# SEGmeterShield15.net
KiCad netlist of a schematic drawn in EAGLE
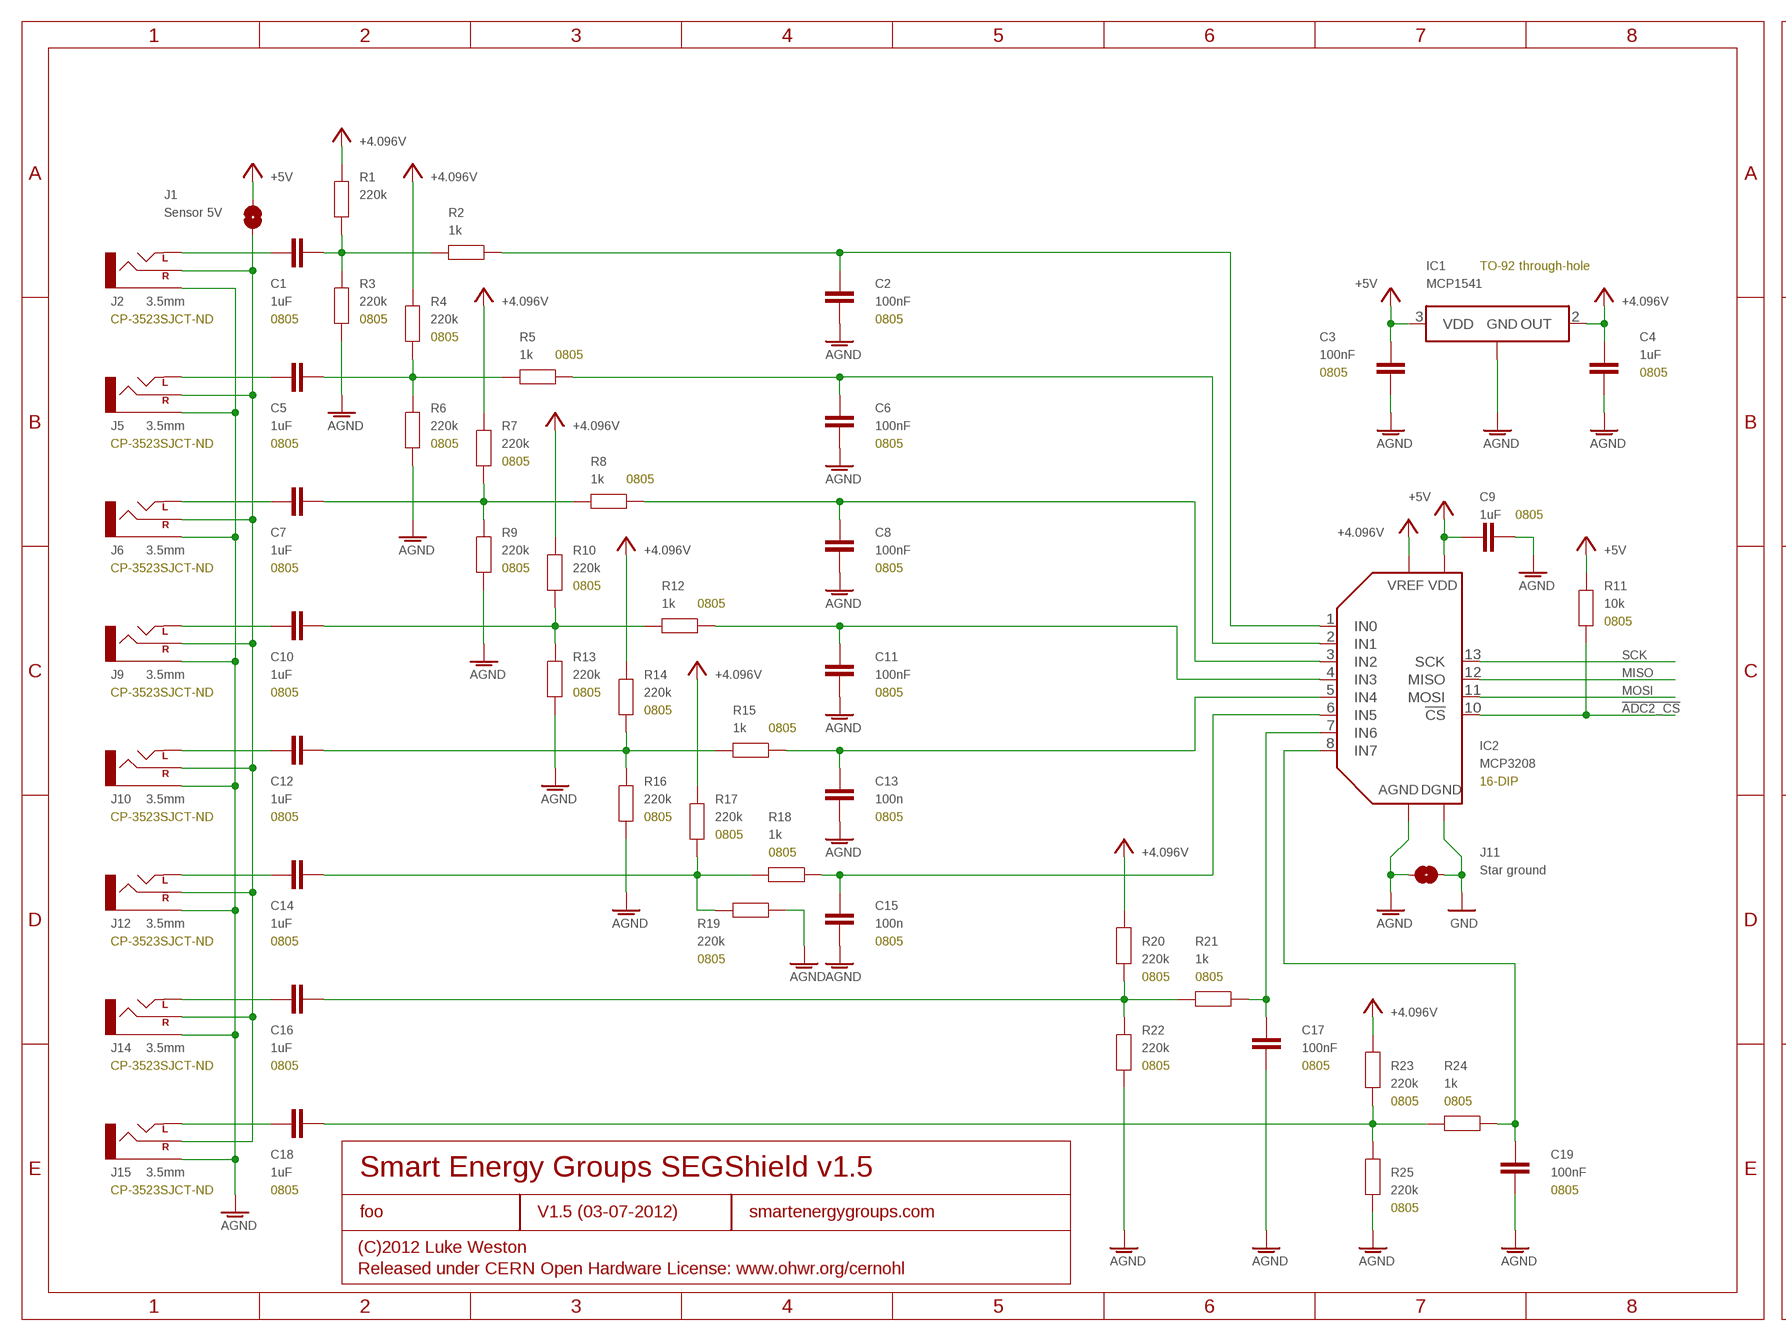
[diagram p0: schematic, sheet 1, part 1 of 2]
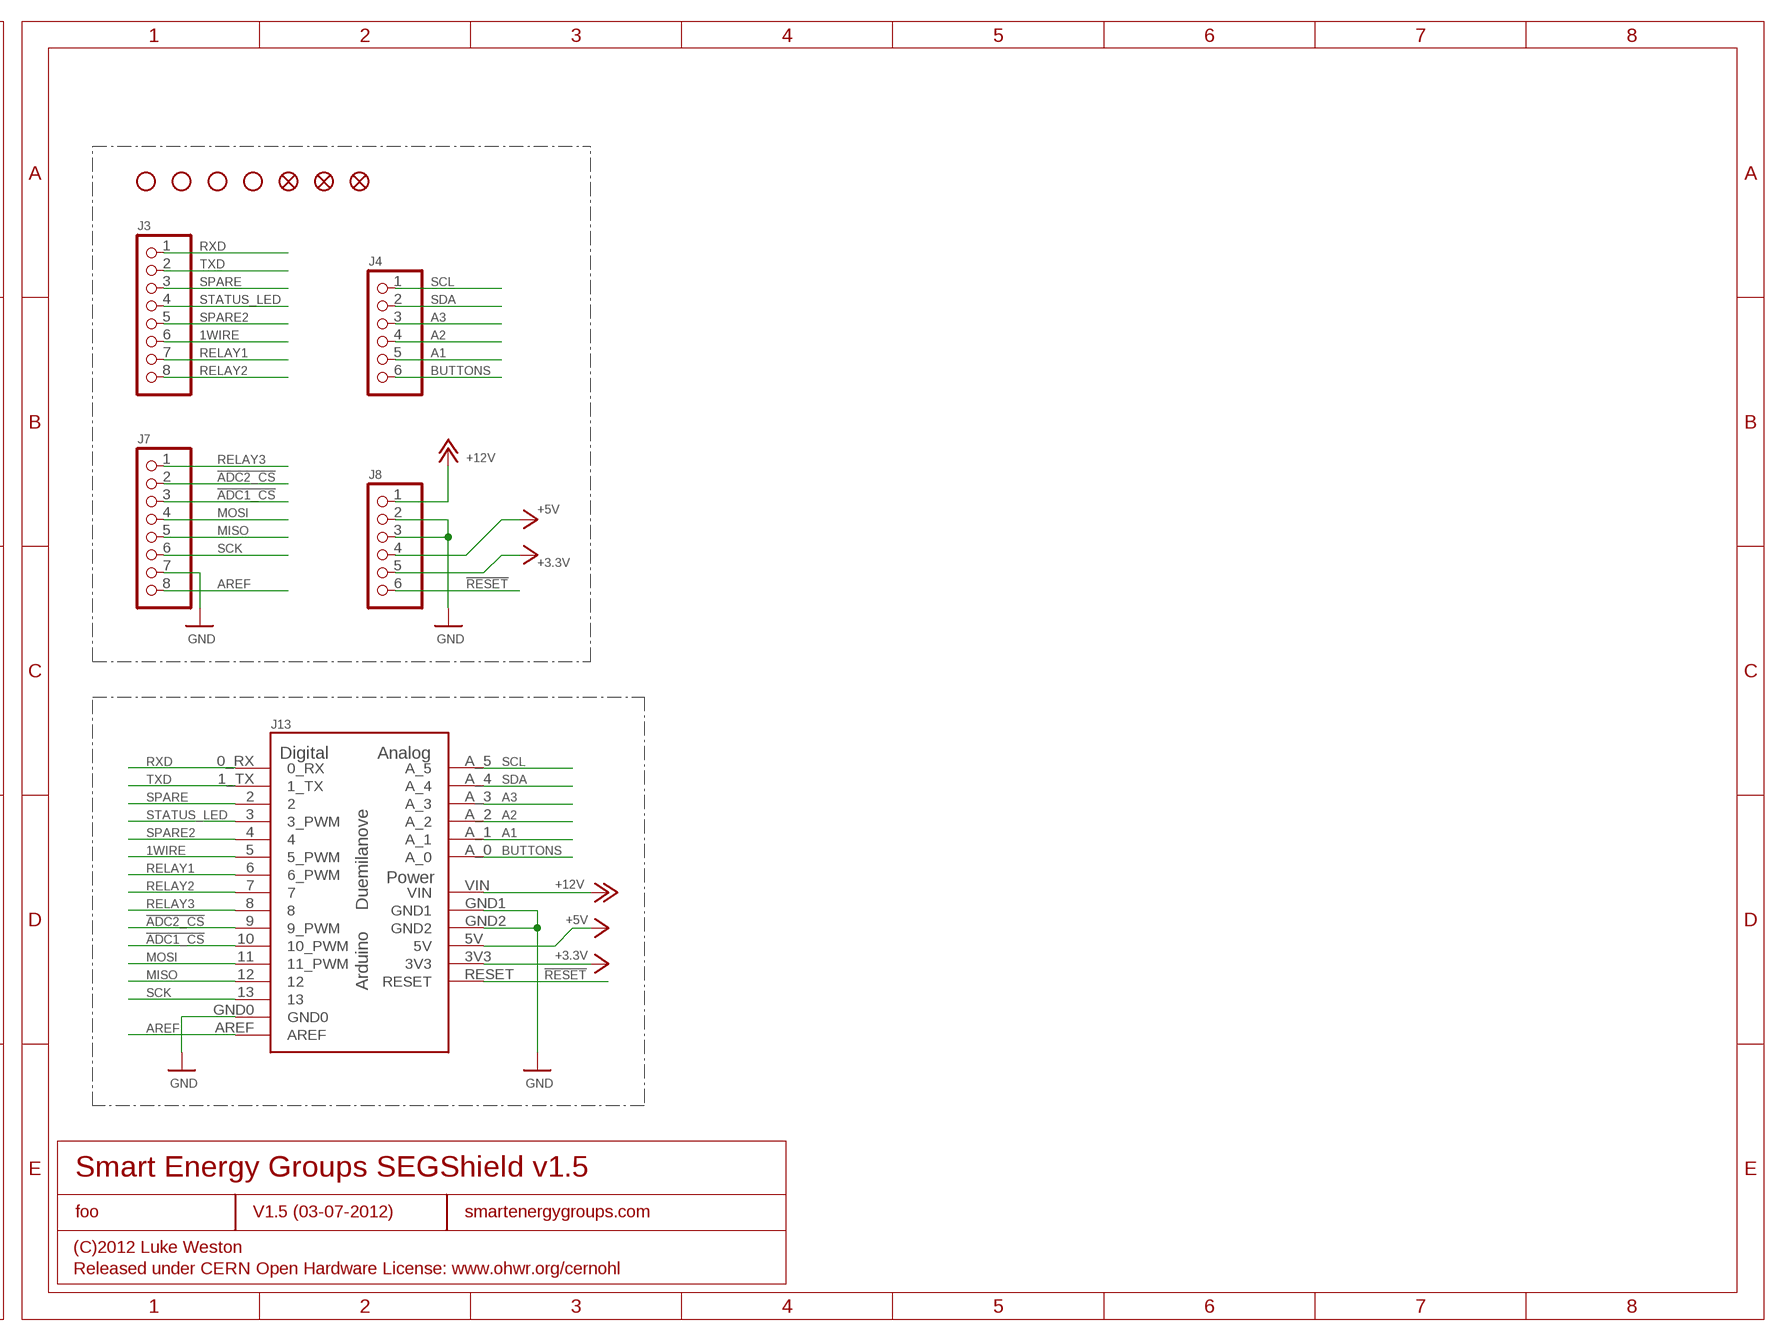
[diagram p1: schematic, sheet 1, part 2 of 2]

(export (version "E")
  (design (tool "Eeschema 10.0.6"))
  (components
    (comp (ref "C1")
      (value "1uF")
      (footprint "eagle-import:0805")
      (libsource (lib "eagle-import") (part "CAP0805"))
    )
    (comp (ref "C2")
      (value "100nF")
      (footprint "eagle-import:0805")
      (libsource (lib "eagle-import") (part "CAP0805"))
    )
    (comp (ref "C3")
      (value "100nF")
      (footprint "eagle-import:0805")
      (libsource (lib "eagle-import") (part "CAP0805"))
    )
    (comp (ref "C4")
      (value "1uF")
      (footprint "eagle-import:0805")
      (libsource (lib "eagle-import") (part "CAP0805"))
    )
    (comp (ref "C5")
      (value "1uF")
      (footprint "eagle-import:0805")
      (libsource (lib "eagle-import") (part "CAP0805"))
    )
    (comp (ref "C6")
      (value "100nF")
      (footprint "eagle-import:0805")
      (libsource (lib "eagle-import") (part "CAP0805"))
    )
    (comp (ref "C7")
      (value "1uF")
      (footprint "eagle-import:0805")
      (libsource (lib "eagle-import") (part "CAP0805"))
    )
    (comp (ref "C8")
      (value "100nF")
      (footprint "eagle-import:0805")
      (libsource (lib "eagle-import") (part "CAP0805"))
    )
    (comp (ref "C9")
      (value "1uF")
      (footprint "eagle-import:0805")
      (libsource (lib "eagle-import") (part "CAP0805"))
    )
    (comp (ref "C10")
      (value "1uF")
      (footprint "eagle-import:0805")
      (libsource (lib "eagle-import") (part "CAP0805"))
    )
    (comp (ref "C11")
      (value "100nF")
      (footprint "eagle-import:0805")
      (libsource (lib "eagle-import") (part "CAP0805"))
    )
    (comp (ref "C12")
      (value "1uF")
      (footprint "eagle-import:0805")
      (libsource (lib "eagle-import") (part "CAP0805"))
    )
    (comp (ref "C13")
      (value "100n")
      (footprint "eagle-import:0805")
      (libsource (lib "eagle-import") (part "CAP0805"))
    )
    (comp (ref "C14")
      (value "1uF")
      (footprint "eagle-import:0805")
      (libsource (lib "eagle-import") (part "CAP0805"))
    )
    (comp (ref "C15")
      (value "100n")
      (footprint "eagle-import:0805")
      (libsource (lib "eagle-import") (part "CAP0805"))
    )
    (comp (ref "C16")
      (value "1uF")
      (footprint "eagle-import:0805")
      (libsource (lib "eagle-import") (part "CAP0805"))
    )
    (comp (ref "C17")
      (value "100nF")
      (footprint "eagle-import:0805")
      (libsource (lib "eagle-import") (part "CAP0805"))
    )
    (comp (ref "C18")
      (value "1uF")
      (footprint "eagle-import:0805")
      (libsource (lib "eagle-import") (part "CAP0805"))
    )
    (comp (ref "C19")
      (value "100nF")
      (footprint "eagle-import:0805")
      (libsource (lib "eagle-import") (part "CAP0805"))
    )
    (comp (ref "IC1")
      (value "MCP1541")
      (footprint "eagle-import:TO92-STRAIGHT")
      (libsource (lib "eagle-import") (part "MCP1541"))
    )
    (comp (ref "IC2")
      (value "MCP3208")
      (footprint "eagle-import:DIL16")
      (libsource (lib "eagle-import") (part "MCP3208DIL"))
    )
    (comp (ref "J1")
      (value "Sensor 5V")
      (footprint "eagle-import:SJ")
      (libsource (lib "eagle-import") (part "SJ"))
    )
    (comp (ref "J2")
      (value "3.5mm")
      (footprint "eagle-import:AUDIO-JACK-3.5MM-SMD")
      (libsource (lib "eagle-import") (part "AUDIO-JACKSMD2"))
    )
    (comp (ref "J3")
      (value "PINHD-1X8")
      (footprint "eagle-import:1X08")
      (libsource (lib "eagle-import") (part "PINHD-1X8"))
    )
    (comp (ref "J4")
      (value "PINHD-1X6")
      (footprint "eagle-import:1X06")
      (libsource (lib "eagle-import") (part "PINHD-1X6"))
    )
    (comp (ref "J5")
      (value "3.5mm")
      (footprint "eagle-import:AUDIO-JACK-3.5MM-SMD")
      (libsource (lib "eagle-import") (part "AUDIO-JACKSMD2"))
    )
    (comp (ref "J6")
      (value "3.5mm")
      (footprint "eagle-import:AUDIO-JACK-3.5MM-SMD")
      (libsource (lib "eagle-import") (part "AUDIO-JACKSMD2"))
    )
    (comp (ref "J7")
      (value "PINHD-1X8")
      (footprint "eagle-import:1X08")
      (libsource (lib "eagle-import") (part "PINHD-1X8"))
    )
    (comp (ref "J8")
      (value "PINHD-1X6")
      (footprint "eagle-import:1X06")
      (libsource (lib "eagle-import") (part "PINHD-1X6"))
    )
    (comp (ref "J9")
      (value "3.5mm")
      (footprint "eagle-import:AUDIO-JACK-3.5MM-SMD")
      (libsource (lib "eagle-import") (part "AUDIO-JACKSMD2"))
    )
    (comp (ref "J10")
      (value "3.5mm")
      (footprint "eagle-import:AUDIO-JACK-3.5MM-SMD")
      (libsource (lib "eagle-import") (part "AUDIO-JACKSMD2"))
    )
    (comp (ref "J11")
      (value "Star ground")
      (footprint "eagle-import:SJ")
      (libsource (lib "eagle-import") (part "SJ"))
    )
    (comp (ref "J12")
      (value "3.5mm")
      (footprint "eagle-import:AUDIO-JACK-3.5MM-SMD")
      (libsource (lib "eagle-import") (part "AUDIO-JACKSMD2"))
    )
    (comp (ref "J13")
      (value "Arduino-compatible headers")
      (footprint "eagle-import:NO-OUTLINE-OCTAGONAL-NOTEXT")
      (libsource (lib "eagle-import") (part "ARDUINO-USBNO-OUTLINE-NO-TEXT-OCTAGONAL"))
    )
    (comp (ref "J14")
      (value "3.5mm")
      (footprint "eagle-import:AUDIO-JACK-3.5MM-SMD")
      (libsource (lib "eagle-import") (part "AUDIO-JACKSMD2"))
    )
    (comp (ref "J15")
      (value "3.5mm")
      (footprint "eagle-import:AUDIO-JACK-3.5MM-SMD")
      (libsource (lib "eagle-import") (part "AUDIO-JACKSMD2"))
    )
    (comp (ref "JP1")
      (value "STAND-OFF")
      (footprint "eagle-import:STAND-OFF")
      (libsource (lib "eagle-import") (part "STAND-OFF"))
    )
    (comp (ref "JP2")
      (value "STAND-OFF")
      (footprint "eagle-import:STAND-OFF")
      (libsource (lib "eagle-import") (part "STAND-OFF"))
    )
    (comp (ref "JP3")
      (value "STAND-OFF")
      (footprint "eagle-import:STAND-OFF")
      (libsource (lib "eagle-import") (part "STAND-OFF"))
    )
    (comp (ref "JP4")
      (value "STAND-OFF")
      (footprint "eagle-import:STAND-OFF")
      (libsource (lib "eagle-import") (part "STAND-OFF"))
    )
    (comp (ref "JP5")
      (value "FIDUCIAL1.5X3")
      (footprint "eagle-import:FIDUCIAL-1.5X3")
      (libsource (lib "eagle-import") (part "FIDUCIAL1.5X3"))
    )
    (comp (ref "JP6")
      (value "FIDUCIAL1.5X3")
      (footprint "eagle-import:FIDUCIAL-1.5X3")
      (libsource (lib "eagle-import") (part "FIDUCIAL1.5X3"))
    )
    (comp (ref "JP7")
      (value "FIDUCIAL1.5X3")
      (footprint "eagle-import:FIDUCIAL-1.5X3")
      (libsource (lib "eagle-import") (part "FIDUCIAL1.5X3"))
    )
    (comp (ref "R1")
      (value "220k")
      (footprint "eagle-import:0805")
      (libsource (lib "eagle-import") (part "RESISTOR0805"))
    )
    (comp (ref "R2")
      (value "1k")
      (footprint "eagle-import:0805")
      (libsource (lib "eagle-import") (part "RESISTOR0805"))
    )
    (comp (ref "R3")
      (value "220k")
      (footprint "eagle-import:0805")
      (libsource (lib "eagle-import") (part "RESISTOR0805"))
    )
    (comp (ref "R4")
      (value "220k")
      (footprint "eagle-import:0805")
      (libsource (lib "eagle-import") (part "RESISTOR0805"))
    )
    (comp (ref "R5")
      (value "1k")
      (footprint "eagle-import:0805")
      (libsource (lib "eagle-import") (part "RESISTOR0805"))
    )
    (comp (ref "R6")
      (value "220k")
      (footprint "eagle-import:0805")
      (libsource (lib "eagle-import") (part "RESISTOR0805"))
    )
    (comp (ref "R7")
      (value "220k")
      (footprint "eagle-import:0805")
      (libsource (lib "eagle-import") (part "RESISTOR0805"))
    )
    (comp (ref "R8")
      (value "1k")
      (footprint "eagle-import:0805")
      (libsource (lib "eagle-import") (part "RESISTOR0805"))
    )
    (comp (ref "R9")
      (value "220k")
      (footprint "eagle-import:0805")
      (libsource (lib "eagle-import") (part "RESISTOR0805"))
    )
    (comp (ref "R10")
      (value "220k")
      (footprint "eagle-import:0805")
      (libsource (lib "eagle-import") (part "RESISTOR0805"))
    )
    (comp (ref "R11")
      (value "10k")
      (footprint "eagle-import:0805")
      (libsource (lib "eagle-import") (part "RESISTOR0805"))
    )
    (comp (ref "R12")
      (value "1k")
      (footprint "eagle-import:0805")
      (libsource (lib "eagle-import") (part "RESISTOR0805"))
    )
    (comp (ref "R13")
      (value "220k")
      (footprint "eagle-import:0805")
      (libsource (lib "eagle-import") (part "RESISTOR0805"))
    )
    (comp (ref "R14")
      (value "220k")
      (footprint "eagle-import:0805")
      (libsource (lib "eagle-import") (part "RESISTOR0805"))
    )
    (comp (ref "R15")
      (value "1k")
      (footprint "eagle-import:0805")
      (libsource (lib "eagle-import") (part "RESISTOR0805"))
    )
    (comp (ref "R16")
      (value "220k")
      (footprint "eagle-import:0805")
      (libsource (lib "eagle-import") (part "RESISTOR0805"))
    )
    (comp (ref "R17")
      (value "220k")
      (footprint "eagle-import:0805")
      (libsource (lib "eagle-import") (part "RESISTOR0805"))
    )
    (comp (ref "R18")
      (value "1k")
      (footprint "eagle-import:0805")
      (libsource (lib "eagle-import") (part "RESISTOR0805"))
    )
    (comp (ref "R19")
      (value "220k")
      (footprint "eagle-import:0805")
      (libsource (lib "eagle-import") (part "RESISTOR0805"))
    )
    (comp (ref "R20")
      (value "220k")
      (footprint "eagle-import:0805")
      (libsource (lib "eagle-import") (part "RESISTOR0805"))
    )
    (comp (ref "R21")
      (value "1k")
      (footprint "eagle-import:0805")
      (libsource (lib "eagle-import") (part "RESISTOR0805"))
    )
    (comp (ref "R22")
      (value "220k")
      (footprint "eagle-import:0805")
      (libsource (lib "eagle-import") (part "RESISTOR0805"))
    )
    (comp (ref "R23")
      (value "220k")
      (footprint "eagle-import:0805")
      (libsource (lib "eagle-import") (part "RESISTOR0805"))
    )
    (comp (ref "R24")
      (value "1k")
      (footprint "eagle-import:0805")
      (libsource (lib "eagle-import") (part "RESISTOR0805"))
    )
    (comp (ref "R25")
      (value "220k")
      (footprint "eagle-import:0805")
      (libsource (lib "eagle-import") (part "RESISTOR0805"))
    )
  )
  (nets
    (net (code "1") (name "+3.3V") (class "Default")
      (node (ref "J13") (pin "3V3") (pinfunction "3V3_3V3") (pintype "power_in"))
      (node (ref "J8") (pin "5") (pinfunction "5_5") (pintype "passive"))
    )
    (net (code "2") (name "+4.096V") (class "Default")
      (node (ref "C4") (pin "2") (pinfunction "2_2") (pintype "passive"))
      (node (ref "IC1") (pin "2") (pinfunction "OUT_2") (pintype "bidirectional"))
      (node (ref "IC2") (pin "15") (pinfunction "VREF_15") (pintype "bidirectional"))
      (node (ref "R1") (pin "2") (pinfunction "2_2") (pintype "passive"))
      (node (ref "R10") (pin "2") (pinfunction "2_2") (pintype "passive"))
      (node (ref "R14") (pin "2") (pinfunction "2_2") (pintype "passive"))
      (node (ref "R17") (pin "2") (pinfunction "2_2") (pintype "passive"))
      (node (ref "R20") (pin "2") (pinfunction "2_2") (pintype "passive"))
      (node (ref "R23") (pin "2") (pinfunction "2_2") (pintype "passive"))
      (node (ref "R4") (pin "2") (pinfunction "2_2") (pintype "passive"))
      (node (ref "R7") (pin "2") (pinfunction "2_2") (pintype "passive"))
    )
    (net (code "3") (name "+5V") (class "Default")
      (node (ref "C3") (pin "2") (pinfunction "2_2") (pintype "passive"))
      (node (ref "C9") (pin "2") (pinfunction "2_2") (pintype "passive"))
      (node (ref "IC1") (pin "3") (pinfunction "VDD_3") (pintype "bidirectional"))
      (node (ref "IC2") (pin "16") (pinfunction "VDD_16") (pintype "bidirectional"))
      (node (ref "J1") (pin "2") (pinfunction "2_2") (pintype "passive"))
      (node (ref "J13") (pin "5V") (pinfunction "5V_5V") (pintype "power_in"))
      (node (ref "J8") (pin "4") (pinfunction "4_4") (pintype "passive"))
      (node (ref "R11") (pin "2") (pinfunction "2_2") (pintype "passive"))
    )
    (net (code "4") (name "+12V") (class "Default")
      (node (ref "J13") (pin "VIN") (pinfunction "VIN_VIN") (pintype "power_in"))
      (node (ref "J8") (pin "1") (pinfunction "1_1") (pintype "passive"))
    )
    (net (code "5") (name "/1WIRE") (class "Default")
      (node (ref "J13") (pin "5") (pinfunction "5_PWM_5") (pintype "bidirectional"))
      (node (ref "J3") (pin "6") (pinfunction "6_6") (pintype "passive"))
    )
    (net (code "6") (name "/A1") (class "Default")
      (node (ref "J13") (pin "A_1") (pinfunction "A_1_A_1") (pintype "input"))
      (node (ref "J4") (pin "5") (pinfunction "5_5") (pintype "passive"))
    )
    (net (code "7") (name "/A2") (class "Default")
      (node (ref "J13") (pin "A_2") (pinfunction "A_2_A_2") (pintype "input"))
      (node (ref "J4") (pin "4") (pinfunction "4_4") (pintype "passive"))
    )
    (net (code "8") (name "/A3") (class "Default")
      (node (ref "J13") (pin "A_3") (pinfunction "A_3_A_3") (pintype "input"))
      (node (ref "J4") (pin "3") (pinfunction "3_3") (pintype "passive"))
    )
    (net (code "9") (name "/AREF") (class "Default")
      (node (ref "J13") (pin "AREF") (pinfunction "AREF_AREF") (pintype "bidirectional"))
      (node (ref "J7") (pin "8") (pinfunction "8_8") (pintype "passive"))
    )
    (net (code "10") (name "/BUTTONS") (class "Default")
      (node (ref "J13") (pin "A_0") (pinfunction "A_0_A_0") (pintype "input"))
      (node (ref "J4") (pin "6") (pinfunction "6_6") (pintype "passive"))
    )
    (net (code "11") (name "/MISO") (class "Default")
      (node (ref "IC2") (pin "12") (pinfunction "MISO_12") (pintype "bidirectional"))
      (node (ref "J13") (pin "12") (pinfunction "12_12") (pintype "bidirectional"))
      (node (ref "J7") (pin "5") (pinfunction "5_5") (pintype "passive"))
    )
    (net (code "12") (name "/MOSI") (class "Default")
      (node (ref "IC2") (pin "11") (pinfunction "MOSI_11") (pintype "bidirectional"))
      (node (ref "J13") (pin "11") (pinfunction "11_PWM_11") (pintype "bidirectional"))
      (node (ref "J7") (pin "4") (pinfunction "4_4") (pintype "passive"))
    )
    (net (code "13") (name "/RELAY1") (class "Default")
      (node (ref "J13") (pin "6") (pinfunction "6_PWM_6") (pintype "bidirectional"))
      (node (ref "J3") (pin "7") (pinfunction "7_7") (pintype "passive"))
    )
    (net (code "14") (name "/RELAY2") (class "Default")
      (node (ref "J13") (pin "7") (pinfunction "7_7") (pintype "bidirectional"))
      (node (ref "J3") (pin "8") (pinfunction "8_8") (pintype "passive"))
    )
    (net (code "15") (name "/RELAY3") (class "Default")
      (node (ref "J13") (pin "8") (pinfunction "8_8") (pintype "bidirectional"))
      (node (ref "J7") (pin "1") (pinfunction "1_1") (pintype "passive"))
    )
    (net (code "16") (name "/RXD") (class "Default")
      (node (ref "J13") (pin "0_RX") (pinfunction "0_RX_0_RX") (pintype "bidirectional"))
      (node (ref "J3") (pin "1") (pinfunction "1_1") (pintype "passive"))
    )
    (net (code "17") (name "/SCK") (class "Default")
      (node (ref "IC2") (pin "13") (pinfunction "SCK_13") (pintype "bidirectional"))
      (node (ref "J13") (pin "13") (pinfunction "13_13") (pintype "bidirectional"))
      (node (ref "J7") (pin "6") (pinfunction "6_6") (pintype "passive"))
    )
    (net (code "18") (name "/SCL") (class "Default")
      (node (ref "J13") (pin "A_5") (pinfunction "A_5_A_5") (pintype "input"))
      (node (ref "J4") (pin "1") (pinfunction "1_1") (pintype "passive"))
    )
    (net (code "19") (name "/SDA") (class "Default")
      (node (ref "J13") (pin "A_4") (pinfunction "A_4_A_4") (pintype "input"))
      (node (ref "J4") (pin "2") (pinfunction "2_2") (pintype "passive"))
    )
    (net (code "20") (name "/SPARE") (class "Default")
      (node (ref "J13") (pin "2") (pinfunction "2_2") (pintype "bidirectional"))
      (node (ref "J3") (pin "3") (pinfunction "3_3") (pintype "passive"))
    )
    (net (code "21") (name "/SPARE2") (class "Default")
      (node (ref "J13") (pin "4") (pinfunction "4_4") (pintype "bidirectional"))
      (node (ref "J3") (pin "5") (pinfunction "5_5") (pintype "passive"))
    )
    (net (code "22") (name "/STATUS_LED") (class "Default")
      (node (ref "J13") (pin "3") (pinfunction "3_PWM_3") (pintype "bidirectional"))
      (node (ref "J3") (pin "4") (pinfunction "4_4") (pintype "passive"))
    )
    (net (code "23") (name "/TXD") (class "Default")
      (node (ref "J13") (pin "1_TX") (pinfunction "1_TX_1_TX") (pintype "bidirectional"))
      (node (ref "J3") (pin "2") (pinfunction "2_2") (pintype "passive"))
    )
    (net (code "24") (name "/~{ADC1_CS}") (class "Default")
      (node (ref "J13") (pin "10") (pinfunction "10_PWM_10") (pintype "bidirectional"))
      (node (ref "J7") (pin "3") (pinfunction "3_3") (pintype "passive"))
    )
    (net (code "25") (name "/~{ADC2_CS}") (class "Default")
      (node (ref "IC2") (pin "10") (pinfunction "~{CS}_10") (pintype "bidirectional"))
      (node (ref "J13") (pin "9") (pinfunction "9_PWM_9") (pintype "bidirectional"))
      (node (ref "J7") (pin "2") (pinfunction "2_2") (pintype "passive"))
      (node (ref "R11") (pin "1") (pinfunction "1_1") (pintype "passive"))
    )
    (net (code "26") (name "/~{RESET}") (class "Default")
      (node (ref "J13") (pin "RESET") (pinfunction "RESET_RESET") (pintype "input"))
      (node (ref "J8") (pin "6") (pinfunction "6_6") (pintype "passive"))
    )
    (net (code "27") (name "AGND") (class "Default")
      (node (ref "C11") (pin "1") (pinfunction "1_1") (pintype "passive"))
      (node (ref "C13") (pin "1") (pinfunction "1_1") (pintype "passive"))
      (node (ref "C15") (pin "1") (pinfunction "1_1") (pintype "passive"))
      (node (ref "C17") (pin "1") (pinfunction "1_1") (pintype "passive"))
      (node (ref "C19") (pin "1") (pinfunction "1_1") (pintype "passive"))
      (node (ref "C2") (pin "1") (pinfunction "1_1") (pintype "passive"))
      (node (ref "C3") (pin "1") (pinfunction "1_1") (pintype "passive"))
      (node (ref "C4") (pin "1") (pinfunction "1_1") (pintype "passive"))
      (node (ref "C6") (pin "1") (pinfunction "1_1") (pintype "passive"))
      (node (ref "C8") (pin "1") (pinfunction "1_1") (pintype "passive"))
      (node (ref "C9") (pin "1") (pinfunction "1_1") (pintype "passive"))
      (node (ref "IC1") (pin "1") (pinfunction "GND_1") (pintype "bidirectional"))
      (node (ref "IC2") (pin "14") (pinfunction "AGND_14") (pintype "bidirectional"))
      (node (ref "J10") (pin "SLEEVE") (pinfunction "SLEEVE_SLEEVE") (pintype "bidirectional"))
      (node (ref "J11") (pin "2") (pinfunction "2_2") (pintype "passive"))
      (node (ref "J12") (pin "SLEEVE") (pinfunction "SLEEVE_SLEEVE") (pintype "bidirectional"))
      (node (ref "J14") (pin "SLEEVE") (pinfunction "SLEEVE_SLEEVE") (pintype "bidirectional"))
      (node (ref "J15") (pin "SLEEVE") (pinfunction "SLEEVE_SLEEVE") (pintype "bidirectional"))
      (node (ref "J2") (pin "SLEEVE") (pinfunction "SLEEVE_SLEEVE") (pintype "bidirectional"))
      (node (ref "J5") (pin "SLEEVE") (pinfunction "SLEEVE_SLEEVE") (pintype "bidirectional"))
      (node (ref "J6") (pin "SLEEVE") (pinfunction "SLEEVE_SLEEVE") (pintype "bidirectional"))
      (node (ref "J9") (pin "SLEEVE") (pinfunction "SLEEVE_SLEEVE") (pintype "bidirectional"))
      (node (ref "R13") (pin "1") (pinfunction "1_1") (pintype "passive"))
      (node (ref "R16") (pin "1") (pinfunction "1_1") (pintype "passive"))
      (node (ref "R19") (pin "1") (pinfunction "1_1") (pintype "passive"))
      (node (ref "R22") (pin "1") (pinfunction "1_1") (pintype "passive"))
      (node (ref "R25") (pin "1") (pinfunction "1_1") (pintype "passive"))
      (node (ref "R3") (pin "1") (pinfunction "1_1") (pintype "passive"))
      (node (ref "R6") (pin "1") (pinfunction "1_1") (pintype "passive"))
      (node (ref "R9") (pin "1") (pinfunction "1_1") (pintype "passive"))
    )
    (net (code "28") (name "GND") (class "Default")
      (node (ref "IC2") (pin "9") (pinfunction "DGND_9") (pintype "bidirectional"))
      (node (ref "J11") (pin "1") (pinfunction "1_1") (pintype "passive"))
      (node (ref "J13") (pin "GND0") (pinfunction "GND0_GND0") (pintype "power_in"))
      (node (ref "J13") (pin "GND1") (pinfunction "GND1_GND1") (pintype "power_in"))
      (node (ref "J13") (pin "GND2") (pinfunction "GND2_GND2") (pintype "power_in"))
      (node (ref "J7") (pin "7") (pinfunction "7_7") (pintype "passive"))
      (node (ref "J8") (pin "2") (pinfunction "2_2") (pintype "passive"))
      (node (ref "J8") (pin "3") (pinfunction "3_3") (pintype "passive"))
    )
    (net (code "29") (name "Net-(C1-Pad2)") (class "Default")
      (node (ref "C1") (pin "2") (pinfunction "2_2") (pintype "passive"))
      (node (ref "R1") (pin "1") (pinfunction "1_1") (pintype "passive"))
      (node (ref "R2") (pin "2") (pinfunction "2_2") (pintype "passive"))
      (node (ref "R3") (pin "2") (pinfunction "2_2") (pintype "passive"))
    )
    (net (code "30") (name "Net-(C5-Pad2)") (class "Default")
      (node (ref "C5") (pin "2") (pinfunction "2_2") (pintype "passive"))
      (node (ref "R4") (pin "1") (pinfunction "1_1") (pintype "passive"))
      (node (ref "R5") (pin "2") (pinfunction "2_2") (pintype "passive"))
      (node (ref "R6") (pin "2") (pinfunction "2_2") (pintype "passive"))
    )
    (net (code "31") (name "Net-(C7-Pad2)") (class "Default")
      (node (ref "C7") (pin "2") (pinfunction "2_2") (pintype "passive"))
      (node (ref "R7") (pin "1") (pinfunction "1_1") (pintype "passive"))
      (node (ref "R8") (pin "2") (pinfunction "2_2") (pintype "passive"))
      (node (ref "R9") (pin "2") (pinfunction "2_2") (pintype "passive"))
    )
    (net (code "32") (name "Net-(C10-Pad2)") (class "Default")
      (node (ref "C10") (pin "2") (pinfunction "2_2") (pintype "passive"))
      (node (ref "R10") (pin "1") (pinfunction "1_1") (pintype "passive"))
      (node (ref "R12") (pin "2") (pinfunction "2_2") (pintype "passive"))
      (node (ref "R13") (pin "2") (pinfunction "2_2") (pintype "passive"))
    )
    (net (code "33") (name "Net-(C12-Pad2)") (class "Default")
      (node (ref "C12") (pin "2") (pinfunction "2_2") (pintype "passive"))
      (node (ref "R14") (pin "1") (pinfunction "1_1") (pintype "passive"))
      (node (ref "R15") (pin "2") (pinfunction "2_2") (pintype "passive"))
      (node (ref "R16") (pin "2") (pinfunction "2_2") (pintype "passive"))
    )
    (net (code "34") (name "Net-(C14-Pad2)") (class "Default")
      (node (ref "C14") (pin "2") (pinfunction "2_2") (pintype "passive"))
      (node (ref "R17") (pin "1") (pinfunction "1_1") (pintype "passive"))
      (node (ref "R18") (pin "2") (pinfunction "2_2") (pintype "passive"))
      (node (ref "R19") (pin "2") (pinfunction "2_2") (pintype "passive"))
    )
    (net (code "35") (name "Net-(C16-Pad2)") (class "Default")
      (node (ref "C16") (pin "2") (pinfunction "2_2") (pintype "passive"))
      (node (ref "R20") (pin "1") (pinfunction "1_1") (pintype "passive"))
      (node (ref "R21") (pin "2") (pinfunction "2_2") (pintype "passive"))
      (node (ref "R22") (pin "2") (pinfunction "2_2") (pintype "passive"))
    )
    (net (code "36") (name "Net-(C18-Pad2)") (class "Default")
      (node (ref "C18") (pin "2") (pinfunction "2_2") (pintype "passive"))
      (node (ref "R23") (pin "1") (pinfunction "1_1") (pintype "passive"))
      (node (ref "R24") (pin "2") (pinfunction "2_2") (pintype "passive"))
      (node (ref "R25") (pin "2") (pinfunction "2_2") (pintype "passive"))
    )
    (net (code "37") (name "Net-(IC2-IN0)") (class "Default")
      (node (ref "C2") (pin "2") (pinfunction "2_2") (pintype "passive"))
      (node (ref "IC2") (pin "1") (pinfunction "IN0_1") (pintype "bidirectional"))
      (node (ref "R2") (pin "1") (pinfunction "1_1") (pintype "passive"))
    )
    (net (code "38") (name "Net-(IC2-IN1)") (class "Default")
      (node (ref "C6") (pin "2") (pinfunction "2_2") (pintype "passive"))
      (node (ref "IC2") (pin "2") (pinfunction "IN1_2") (pintype "bidirectional"))
      (node (ref "R5") (pin "1") (pinfunction "1_1") (pintype "passive"))
    )
    (net (code "39") (name "Net-(IC2-IN2)") (class "Default")
      (node (ref "C8") (pin "2") (pinfunction "2_2") (pintype "passive"))
      (node (ref "IC2") (pin "3") (pinfunction "IN2_3") (pintype "bidirectional"))
      (node (ref "R8") (pin "1") (pinfunction "1_1") (pintype "passive"))
    )
    (net (code "40") (name "Net-(IC2-IN3)") (class "Default")
      (node (ref "C11") (pin "2") (pinfunction "2_2") (pintype "passive"))
      (node (ref "IC2") (pin "4") (pinfunction "IN3_4") (pintype "bidirectional"))
      (node (ref "R12") (pin "1") (pinfunction "1_1") (pintype "passive"))
    )
    (net (code "41") (name "Net-(IC2-IN4)") (class "Default")
      (node (ref "C13") (pin "2") (pinfunction "2_2") (pintype "passive"))
      (node (ref "IC2") (pin "5") (pinfunction "IN4_5") (pintype "bidirectional"))
      (node (ref "R15") (pin "1") (pinfunction "1_1") (pintype "passive"))
    )
    (net (code "42") (name "Net-(IC2-IN5)") (class "Default")
      (node (ref "C15") (pin "2") (pinfunction "2_2") (pintype "passive"))
      (node (ref "IC2") (pin "6") (pinfunction "IN5_6") (pintype "bidirectional"))
      (node (ref "R18") (pin "1") (pinfunction "1_1") (pintype "passive"))
    )
    (net (code "43") (name "Net-(IC2-IN6)") (class "Default")
      (node (ref "C17") (pin "2") (pinfunction "2_2") (pintype "passive"))
      (node (ref "IC2") (pin "7") (pinfunction "IN6_7") (pintype "bidirectional"))
      (node (ref "R21") (pin "1") (pinfunction "1_1") (pintype "passive"))
    )
    (net (code "44") (name "Net-(IC2-IN7)") (class "Default")
      (node (ref "C19") (pin "2") (pinfunction "2_2") (pintype "passive"))
      (node (ref "IC2") (pin "8") (pinfunction "IN7_8") (pintype "bidirectional"))
      (node (ref "R24") (pin "1") (pinfunction "1_1") (pintype "passive"))
    )
    (net (code "45") (name "Net-(J2-LEFT)") (class "Default")
      (node (ref "C1") (pin "1") (pinfunction "1_1") (pintype "passive"))
      (node (ref "J2") (pin "TIP") (pinfunction "LEFT_TIP") (pintype "bidirectional"))
    )
    (net (code "46") (name "Net-(J5-LEFT)") (class "Default")
      (node (ref "C5") (pin "1") (pinfunction "1_1") (pintype "passive"))
      (node (ref "J5") (pin "TIP") (pinfunction "LEFT_TIP") (pintype "bidirectional"))
    )
    (net (code "47") (name "Net-(J6-LEFT)") (class "Default")
      (node (ref "C7") (pin "1") (pinfunction "1_1") (pintype "passive"))
      (node (ref "J6") (pin "TIP") (pinfunction "LEFT_TIP") (pintype "bidirectional"))
    )
    (net (code "48") (name "Net-(J9-LEFT)") (class "Default")
      (node (ref "C10") (pin "1") (pinfunction "1_1") (pintype "passive"))
      (node (ref "J9") (pin "TIP") (pinfunction "LEFT_TIP") (pintype "bidirectional"))
    )
    (net (code "49") (name "Net-(J10-LEFT)") (class "Default")
      (node (ref "C12") (pin "1") (pinfunction "1_1") (pintype "passive"))
      (node (ref "J10") (pin "TIP") (pinfunction "LEFT_TIP") (pintype "bidirectional"))
    )
    (net (code "50") (name "Net-(J10-RIGHT)") (class "Default")
      (node (ref "J1") (pin "1") (pinfunction "1_1") (pintype "passive"))
      (node (ref "J10") (pin "RING") (pinfunction "RIGHT_RING") (pintype "bidirectional"))
      (node (ref "J12") (pin "RING") (pinfunction "RIGHT_RING") (pintype "bidirectional"))
      (node (ref "J14") (pin "RING") (pinfunction "RIGHT_RING") (pintype "bidirectional"))
      (node (ref "J15") (pin "RING") (pinfunction "RIGHT_RING") (pintype "bidirectional"))
      (node (ref "J2") (pin "RING") (pinfunction "RIGHT_RING") (pintype "bidirectional"))
      (node (ref "J5") (pin "RING") (pinfunction "RIGHT_RING") (pintype "bidirectional"))
      (node (ref "J6") (pin "RING") (pinfunction "RIGHT_RING") (pintype "bidirectional"))
      (node (ref "J9") (pin "RING") (pinfunction "RIGHT_RING") (pintype "bidirectional"))
    )
    (net (code "51") (name "Net-(J12-LEFT)") (class "Default")
      (node (ref "C14") (pin "1") (pinfunction "1_1") (pintype "passive"))
      (node (ref "J12") (pin "TIP") (pinfunction "LEFT_TIP") (pintype "bidirectional"))
    )
    (net (code "52") (name "Net-(J14-LEFT)") (class "Default")
      (node (ref "C16") (pin "1") (pinfunction "1_1") (pintype "passive"))
      (node (ref "J14") (pin "TIP") (pinfunction "LEFT_TIP") (pintype "bidirectional"))
    )
    (net (code "53") (name "Net-(J15-LEFT)") (class "Default")
      (node (ref "C18") (pin "1") (pinfunction "1_1") (pintype "passive"))
      (node (ref "J15") (pin "TIP") (pinfunction "LEFT_TIP") (pintype "bidirectional"))
    )
  )
)
